# CristmasVillage_Driver_1-0.net
KiCad netlist of a schematic drawn in EAGLE
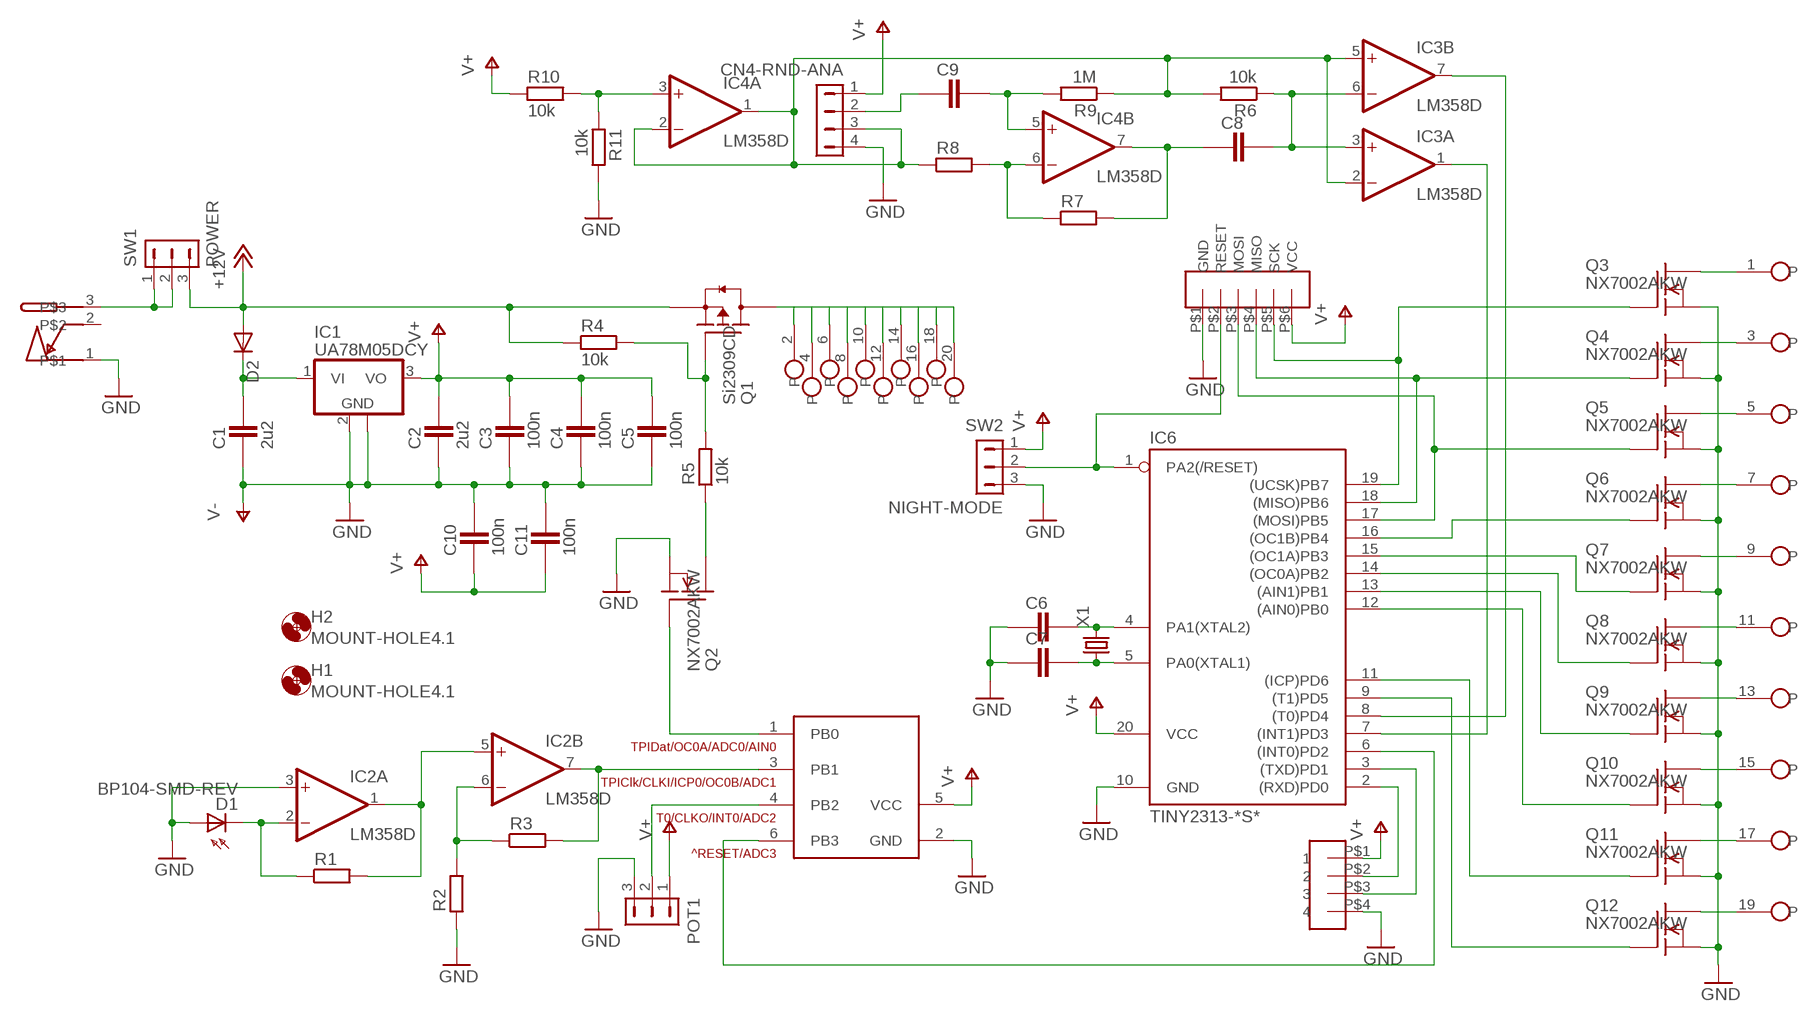
[diagram p0: schematic, sheet 1]

(export (version "E")
  (design (tool "Eeschema 10.0.6"))
  (components
    (comp (ref "C1")
      (value "2u2")
      (footprint "eagle-import:CAPC3215X168N")
      (libsource (lib "eagle-import") (part "CAPACITOR_1206"))
    )
    (comp (ref "C2")
      (value "2u2")
      (footprint "eagle-import:CAPC3215X168N")
      (libsource (lib "eagle-import") (part "CAPACITOR_1206"))
    )
    (comp (ref "C3")
      (value "100n")
      (footprint "eagle-import:CAPC1608X92N")
      (libsource (lib "eagle-import") (part "CAPACITOR_0603"))
    )
    (comp (ref "C4")
      (value "100n")
      (footprint "eagle-import:CAPC1608X92N")
      (libsource (lib "eagle-import") (part "CAPACITOR_0603"))
    )
    (comp (ref "C5")
      (value "100n")
      (footprint "eagle-import:CAPC1608X92N")
      (libsource (lib "eagle-import") (part "CAPACITOR_0603"))
    )
    (comp (ref "C6")
      (value "CAPACITOR_0603")
      (footprint "eagle-import:CAPC1608X92N")
      (libsource (lib "eagle-import") (part "CAPACITOR_0603"))
    )
    (comp (ref "C7")
      (value "CAPACITOR_0603")
      (footprint "eagle-import:CAPC1608X92N")
      (libsource (lib "eagle-import") (part "CAPACITOR_0603"))
    )
    (comp (ref "C8")
      (value "CAPACITOR_1206")
      (footprint "eagle-import:CAPC3215X168N")
      (libsource (lib "eagle-import") (part "CAPACITOR_1206"))
    )
    (comp (ref "C9")
      (value "CAPACITOR_1206")
      (footprint "eagle-import:CAPC3215X168N")
      (libsource (lib "eagle-import") (part "CAPACITOR_1206"))
    )
    (comp (ref "C10")
      (value "100n")
      (footprint "eagle-import:CAPC1608X92N")
      (libsource (lib "eagle-import") (part "CAPACITOR_0603"))
    )
    (comp (ref "C11")
      (value "100n")
      (footprint "eagle-import:CAPC1608X92N")
      (libsource (lib "eagle-import") (part "CAPACITOR_0603"))
    )
    (comp (ref "CN1")
      (value "MJ-180SMT")
      (footprint "eagle-import:MJ-180SMT")
      (libsource (lib "eagle-import") (part "MJ-180SMT"))
    )
    (comp (ref "CN2-PROG")
      (value "JST-6PSPI-SIDE-S6B")
      (footprint "eagle-import:6P-H")
      (libsource (lib "eagle-import") (part "JST-6PSPI-SIDE-S6B"))
    )
    (comp (ref "CN3-SERIAL")
      (value "JST-4PSIDE-S4B")
      (footprint "eagle-import:4P-H")
      (libsource (lib "eagle-import") (part "JST-4PSIDE-S4B"))
    )
    (comp (ref "CN4-RND-ANA")
      (value "HDR-1X4-SIP-100")
      (footprint "eagle-import:SIP-100-4V")
      (libsource (lib "eagle-import") (part "HDR-1X4-SIP-100"))
    )
    (comp (ref "CN5-LEDSTRIPS")
      (value "HDR_2X10_SIDE-MOUNT")
      (footprint "eagle-import:20PIN-10TOP-10BOT")
      (libsource (lib "eagle-import") (part "HDR_2X10_SIDE-MOUNT"))
    )
    (comp (ref "D1")
      (value "BP104-SMD-REV")
      (footprint "eagle-import:BR104SMDREV")
      (libsource (lib "eagle-import") (part "BP104-SMD-REV"))
    )
    (comp (ref "D2")
      (value "DIODE-MINIMELF")
      (footprint "eagle-import:MINIMELF")
      (libsource (lib "eagle-import") (part "DIODE-MINIMELF"))
    )
    (comp (ref "H1")
      (value "MOUNT-HOLE4.1")
      (footprint "eagle-import:4,1")
      (libsource (lib "eagle-import") (part "MOUNT-HOLE4.1"))
    )
    (comp (ref "H2")
      (value "MOUNT-HOLE4.1")
      (footprint "eagle-import:4,1")
      (libsource (lib "eagle-import") (part "MOUNT-HOLE4.1"))
    )
    (comp (ref "IC1")
      (value "UA78M05DCY")
      (footprint "eagle-import:SOT223")
      (libsource (lib "eagle-import") (part "UA78MDCY05"))
    )
    (comp (ref "IC2")
      (value "LM358D")
      (footprint "eagle-import:SO08")
      (libsource (lib "eagle-import") (part "LM358D"))
    )
    (comp (ref "IC3")
      (value "LM358D")
      (footprint "eagle-import:SO08")
      (libsource (lib "eagle-import") (part "LM358D"))
    )
    (comp (ref "IC4")
      (value "LM358D")
      (footprint "eagle-import:SO08")
      (libsource (lib "eagle-import") (part "LM358D"))
    )
    (comp (ref "IC5")
      (value "ATTINY-4/5/9/10")
      (footprint "eagle-import:SOT23-6")
      (libsource (lib "eagle-import") (part "ATTINY-4/5/9/10"))
    )
    (comp (ref "IC6")
      (value "TINY2313-*S*")
      (footprint "eagle-import:SO20L$")
      (libsource (lib "eagle-import") (part "TINY2313-S"))
    )
    (comp (ref "POT1")
      (value "HDR-1X3-MTE-100")
      (footprint "eagle-import:MTE-100-3V")
      (libsource (lib "eagle-import") (part "HDR-1X3-MTE-100"))
    )
    (comp (ref "Q1")
      (value "Si2309CD")
      (footprint "eagle-import:SOT95P280X135-3N")
      (libsource (lib "eagle-import") (part "MOSFET-PCH_SOT-23"))
    )
    (comp (ref "Q2")
      (value "NX7002AKW")
      (footprint "eagle-import:SOT323R")
      (libsource (lib "eagle-import") (part "NX7002AKW"))
    )
    (comp (ref "Q3")
      (value "NX7002AKW")
      (footprint "eagle-import:SOT323R")
      (libsource (lib "eagle-import") (part "NX7002AKW"))
    )
    (comp (ref "Q4")
      (value "NX7002AKW")
      (footprint "eagle-import:SOT323R")
      (libsource (lib "eagle-import") (part "NX7002AKW"))
    )
    (comp (ref "Q5")
      (value "NX7002AKW")
      (footprint "eagle-import:SOT323R")
      (libsource (lib "eagle-import") (part "NX7002AKW"))
    )
    (comp (ref "Q6")
      (value "NX7002AKW")
      (footprint "eagle-import:SOT323R")
      (libsource (lib "eagle-import") (part "NX7002AKW"))
    )
    (comp (ref "Q7")
      (value "NX7002AKW")
      (footprint "eagle-import:SOT323R")
      (libsource (lib "eagle-import") (part "NX7002AKW"))
    )
    (comp (ref "Q8")
      (value "NX7002AKW")
      (footprint "eagle-import:SOT323R")
      (libsource (lib "eagle-import") (part "NX7002AKW"))
    )
    (comp (ref "Q9")
      (value "NX7002AKW")
      (footprint "eagle-import:SOT323R")
      (libsource (lib "eagle-import") (part "NX7002AKW"))
    )
    (comp (ref "Q10")
      (value "NX7002AKW")
      (footprint "eagle-import:SOT323R")
      (libsource (lib "eagle-import") (part "NX7002AKW"))
    )
    (comp (ref "Q11")
      (value "NX7002AKW")
      (footprint "eagle-import:SOT323R")
      (libsource (lib "eagle-import") (part "NX7002AKW"))
    )
    (comp (ref "Q12")
      (value "NX7002AKW")
      (footprint "eagle-import:SOT323R")
      (libsource (lib "eagle-import") (part "NX7002AKW"))
    )
    (comp (ref "R1")
      (value "RESISTOR_0603")
      (footprint "eagle-import:RESC1608X55N")
      (libsource (lib "eagle-import") (part "RESISTOR_0603"))
    )
    (comp (ref "R2")
      (value "RESISTOR_0603")
      (footprint "eagle-import:RESC1608X55N")
      (libsource (lib "eagle-import") (part "RESISTOR_0603"))
    )
    (comp (ref "R3")
      (value "RESISTOR_0603")
      (footprint "eagle-import:RESC1608X55N")
      (libsource (lib "eagle-import") (part "RESISTOR_0603"))
    )
    (comp (ref "R4")
      (value "10k")
      (footprint "eagle-import:RESC1608X55N")
      (libsource (lib "eagle-import") (part "RESISTOR_0603"))
    )
    (comp (ref "R5")
      (value "10k")
      (footprint "eagle-import:RESC1608X55N")
      (libsource (lib "eagle-import") (part "RESISTOR_0603"))
    )
    (comp (ref "R6")
      (value "10k")
      (footprint "eagle-import:RESC1608X55N")
      (libsource (lib "eagle-import") (part "RESISTOR_0603"))
    )
    (comp (ref "R7")
      (value "RESISTOR_0603")
      (footprint "eagle-import:RESC1608X55N")
      (libsource (lib "eagle-import") (part "RESISTOR_0603"))
    )
    (comp (ref "R8")
      (value "RESISTOR_0603")
      (footprint "eagle-import:RESC1608X55N")
      (libsource (lib "eagle-import") (part "RESISTOR_0603"))
    )
    (comp (ref "R9")
      (value "1M")
      (footprint "eagle-import:RESC1608X55N")
      (libsource (lib "eagle-import") (part "RESISTOR_0603"))
    )
    (comp (ref "R10")
      (value "10k")
      (footprint "eagle-import:RESC1608X55N")
      (libsource (lib "eagle-import") (part "RESISTOR_0603"))
    )
    (comp (ref "R11")
      (value "10k")
      (footprint "eagle-import:RESC1608X55N")
      (libsource (lib "eagle-import") (part "RESISTOR_0603"))
    )
    (comp (ref "SW1")
      (value "POWER")
      (footprint "eagle-import:MTE-100-3V")
      (libsource (lib "eagle-import") (part "HDR-1X3-MTE-100"))
    )
    (comp (ref "SW2")
      (value "NIGHT-MODE")
      (footprint "eagle-import:MTE-100-3V")
      (libsource (lib "eagle-import") (part "HDR-1X3-MTE-100"))
    )
    (comp (ref "X1")
      (value "CRYSTALSM49")
      (footprint "eagle-import:SM49")
      (libsource (lib "eagle-import") (part "CRYSTALSM49"))
    )
  )
  (nets
    (net (code "1") (name "+12V") (class "Default")
      (node (ref "D2") (pin "A") (pinfunction "A_A") (pintype "passive"))
      (node (ref "Q1") (pin "2") (pinfunction "S_2") (pintype "passive"))
      (node (ref "R4") (pin "1") (pinfunction "1_1") (pintype "passive"))
      (node (ref "SW1") (pin "3") (pinfunction "3_3") (pintype "passive"))
    )
    (net (code "2") (name "GND") (class "Default")
      (node (ref "C1") (pin "1") (pinfunction "1_1") (pintype "passive"))
      (node (ref "C10") (pin "2") (pinfunction "2_2") (pintype "passive"))
      (node (ref "C11") (pin "2") (pinfunction "2_2") (pintype "passive"))
      (node (ref "C2") (pin "1") (pinfunction "1_1") (pintype "passive"))
      (node (ref "C3") (pin "1") (pinfunction "1_1") (pintype "passive"))
      (node (ref "C4") (pin "1") (pinfunction "1_1") (pintype "passive"))
      (node (ref "C5") (pin "1") (pinfunction "1_1") (pintype "passive"))
      (node (ref "C6") (pin "1") (pinfunction "1_1") (pintype "passive"))
      (node (ref "C7") (pin "1") (pinfunction "1_1") (pintype "passive"))
      (node (ref "CN1") (pin "1") (pinfunction "P$1_1") (pintype "bidirectional"))
      (node (ref "CN2-PROG") (pin "P$1") (pinfunction "GND_P$1") (pintype "bidirectional"))
      (node (ref "CN3-SERIAL") (pin "P$4") (pinfunction "4_P$4") (pintype "bidirectional"))
      (node (ref "CN4-RND-ANA") (pin "4") (pinfunction "4_4") (pintype "passive"))
      (node (ref "D1") (pin "1") (pinfunction "A_1") (pintype "passive"))
      (node (ref "IC1") (pin "2") (pinfunction "GND_2") (pintype "passive"))
      (node (ref "IC1") (pin "4") (pinfunction "GND_4") (pintype "passive"))
      (node (ref "IC2") (pin "3") (pinfunction "+IN_3") (pintype "input"))
      (node (ref "IC5") (pin "2") (pinfunction "GND_2") (pintype "bidirectional"))
      (node (ref "IC6") (pin "10") (pinfunction "GND_10") (pintype "power_in"))
      (node (ref "POT1") (pin "3") (pinfunction "3_3") (pintype "passive"))
      (node (ref "Q10") (pin "2") (pinfunction "S_2") (pintype "passive"))
      (node (ref "Q11") (pin "2") (pinfunction "S_2") (pintype "passive"))
      (node (ref "Q12") (pin "2") (pinfunction "S_2") (pintype "passive"))
      (node (ref "Q2") (pin "2") (pinfunction "S_2") (pintype "passive"))
      (node (ref "Q3") (pin "2") (pinfunction "S_2") (pintype "passive"))
      (node (ref "Q4") (pin "2") (pinfunction "S_2") (pintype "passive"))
      (node (ref "Q5") (pin "2") (pinfunction "S_2") (pintype "passive"))
      (node (ref "Q6") (pin "2") (pinfunction "S_2") (pintype "passive"))
      (node (ref "Q7") (pin "2") (pinfunction "S_2") (pintype "passive"))
      (node (ref "Q8") (pin "2") (pinfunction "S_2") (pintype "passive"))
      (node (ref "Q9") (pin "2") (pinfunction "S_2") (pintype "passive"))
      (node (ref "R11") (pin "2") (pinfunction "2_2") (pintype "passive"))
      (node (ref "R2") (pin "1") (pinfunction "1_1") (pintype "passive"))
      (node (ref "SW2") (pin "3") (pinfunction "3_3") (pintype "passive"))
    )
    (net (code "3") (name "Net-(C9-Pad1)") (class "Default")
      (node (ref "C9") (pin "1") (pinfunction "1_1") (pintype "passive"))
      (node (ref "CN4-RND-ANA") (pin "2") (pinfunction "2_2") (pintype "passive"))
    )
    (net (code "4") (name "Net-(CN1-P$3)") (class "Default")
      (node (ref "CN1") (pin "3") (pinfunction "P$3_3") (pintype "bidirectional"))
      (node (ref "SW1") (pin "1") (pinfunction "1_1") (pintype "passive"))
      (node (ref "SW1") (pin "2") (pinfunction "2_2") (pintype "passive"))
    )
    (net (code "5") (name "Net-(CN2-PROG-MISO)") (class "Default")
      (node (ref "CN2-PROG") (pin "P$4") (pinfunction "MISO_P$4") (pintype "bidirectional"))
      (node (ref "IC6") (pin "18") (pinfunction "(MISO)PB6_18") (pintype "bidirectional"))
      (node (ref "Q4") (pin "1") (pinfunction "G_1") (pintype "passive"))
    )
    (net (code "6") (name "Net-(CN2-PROG-MOSI)") (class "Default")
      (node (ref "CN2-PROG") (pin "P$3") (pinfunction "MOSI_P$3") (pintype "bidirectional"))
      (node (ref "IC6") (pin "17") (pinfunction "(MOSI)PB5_17") (pintype "bidirectional"))
      (node (ref "Q5") (pin "1") (pinfunction "G_1") (pintype "passive"))
    )
    (net (code "7") (name "Net-(CN2-PROG-RESET)") (class "Default")
      (node (ref "CN2-PROG") (pin "P$2") (pinfunction "RESET_P$2") (pintype "bidirectional"))
      (node (ref "IC6") (pin "1") (pinfunction "PA2(/RESET)_1") (pintype "input"))
      (node (ref "SW2") (pin "2") (pinfunction "2_2") (pintype "passive"))
    )
    (net (code "8") (name "Net-(CN2-PROG-SCK)") (class "Default")
      (node (ref "CN2-PROG") (pin "P$5") (pinfunction "SCK_P$5") (pintype "bidirectional"))
      (node (ref "IC6") (pin "19") (pinfunction "(UCSK)PB7_19") (pintype "bidirectional"))
      (node (ref "Q3") (pin "1") (pinfunction "G_1") (pintype "passive"))
    )
    (net (code "9") (name "Net-(CN3-SERIAL-2)") (class "Default")
      (node (ref "CN3-SERIAL") (pin "P$2") (pinfunction "2_P$2") (pintype "bidirectional"))
      (node (ref "IC6") (pin "2") (pinfunction "(RXD)PD0_2") (pintype "bidirectional"))
    )
    (net (code "10") (name "Net-(CN3-SERIAL-3)") (class "Default")
      (node (ref "CN3-SERIAL") (pin "P$3") (pinfunction "3_P$3") (pintype "bidirectional"))
      (node (ref "IC6") (pin "3") (pinfunction "(TXD)PD1_3") (pintype "bidirectional"))
    )
    (net (code "11") (name "Net-(CN5-LEDSTRIPSA-P)") (class "Default")
      (node (ref "CN5-LEDSTRIPS") (pin "1") (pinfunction "P_1") (pintype "bidirectional"))
      (node (ref "Q3") (pin "3") (pinfunction "D_3") (pintype "passive"))
    )
    (net (code "12") (name "Net-(CN5-LEDSTRIPSB-P)") (class "Default")
      (node (ref "CN5-LEDSTRIPS") (pin "10") (pinfunction "P_10") (pintype "bidirectional"))
      (node (ref "CN5-LEDSTRIPS") (pin "12") (pinfunction "P_12") (pintype "bidirectional"))
      (node (ref "CN5-LEDSTRIPS") (pin "14") (pinfunction "P_14") (pintype "bidirectional"))
      (node (ref "CN5-LEDSTRIPS") (pin "16") (pinfunction "P_16") (pintype "bidirectional"))
      (node (ref "CN5-LEDSTRIPS") (pin "18") (pinfunction "P_18") (pintype "bidirectional"))
      (node (ref "CN5-LEDSTRIPS") (pin "2") (pinfunction "P_2") (pintype "bidirectional"))
      (node (ref "CN5-LEDSTRIPS") (pin "20") (pinfunction "P_20") (pintype "bidirectional"))
      (node (ref "CN5-LEDSTRIPS") (pin "4") (pinfunction "P_4") (pintype "bidirectional"))
      (node (ref "CN5-LEDSTRIPS") (pin "6") (pinfunction "P_6") (pintype "bidirectional"))
      (node (ref "CN5-LEDSTRIPS") (pin "8") (pinfunction "P_8") (pintype "bidirectional"))
      (node (ref "Q1") (pin "3") (pinfunction "D_3") (pintype "passive"))
    )
    (net (code "13") (name "Net-(CN5-LEDSTRIPSC-P)") (class "Default")
      (node (ref "CN5-LEDSTRIPS") (pin "11") (pinfunction "P_11") (pintype "bidirectional"))
      (node (ref "Q8") (pin "3") (pinfunction "D_3") (pintype "passive"))
    )
    (net (code "14") (name "Net-(CN5-LEDSTRIPSE-P)") (class "Default")
      (node (ref "CN5-LEDSTRIPS") (pin "13") (pinfunction "P_13") (pintype "bidirectional"))
      (node (ref "Q9") (pin "3") (pinfunction "D_3") (pintype "passive"))
    )
    (net (code "15") (name "Net-(CN5-LEDSTRIPSG-P)") (class "Default")
      (node (ref "CN5-LEDSTRIPS") (pin "15") (pinfunction "P_15") (pintype "bidirectional"))
      (node (ref "Q10") (pin "3") (pinfunction "D_3") (pintype "passive"))
    )
    (net (code "16") (name "Net-(CN5-LEDSTRIPSI-P)") (class "Default")
      (node (ref "CN5-LEDSTRIPS") (pin "17") (pinfunction "P_17") (pintype "bidirectional"))
      (node (ref "Q11") (pin "3") (pinfunction "D_3") (pintype "passive"))
    )
    (net (code "17") (name "Net-(CN5-LEDSTRIPSK-P)") (class "Default")
      (node (ref "CN5-LEDSTRIPS") (pin "19") (pinfunction "P_19") (pintype "bidirectional"))
      (node (ref "Q12") (pin "3") (pinfunction "D_3") (pintype "passive"))
    )
    (net (code "18") (name "Net-(CN5-LEDSTRIPSN-P)") (class "Default")
      (node (ref "CN5-LEDSTRIPS") (pin "3") (pinfunction "P_3") (pintype "bidirectional"))
      (node (ref "Q4") (pin "3") (pinfunction "D_3") (pintype "passive"))
    )
    (net (code "19") (name "Net-(CN5-LEDSTRIPSP-P)") (class "Default")
      (node (ref "CN5-LEDSTRIPS") (pin "5") (pinfunction "P_5") (pintype "bidirectional"))
      (node (ref "Q5") (pin "3") (pinfunction "D_3") (pintype "passive"))
    )
    (net (code "20") (name "Net-(CN5-LEDSTRIPSR-P)") (class "Default")
      (node (ref "CN5-LEDSTRIPS") (pin "7") (pinfunction "P_7") (pintype "bidirectional"))
      (node (ref "Q6") (pin "3") (pinfunction "D_3") (pintype "passive"))
    )
    (net (code "21") (name "Net-(CN5-LEDSTRIPST-P)") (class "Default")
      (node (ref "CN5-LEDSTRIPS") (pin "9") (pinfunction "P_9") (pintype "bidirectional"))
      (node (ref "Q7") (pin "3") (pinfunction "D_3") (pintype "passive"))
    )
    (net (code "22") (name "Net-(D1-C)") (class "Default")
      (node (ref "D1") (pin "2") (pinfunction "C_2") (pintype "passive"))
      (node (ref "IC2") (pin "2") (pinfunction "-IN_2") (pintype "input"))
      (node (ref "R1") (pin "1") (pinfunction "1_1") (pintype "passive"))
    )
    (net (code "23") (name "Net-(IC1-VI)") (class "Default")
      (node (ref "C1") (pin "2") (pinfunction "2_2") (pintype "passive"))
      (node (ref "D2") (pin "C") (pinfunction "C_C") (pintype "passive"))
      (node (ref "IC1") (pin "1") (pinfunction "VI_1") (pintype "input"))
    )
    (net (code "24") (name "Net-(IC2A-OUT)") (class "Default")
      (node (ref "IC2") (pin "1") (pinfunction "OUT_1") (pintype "output"))
      (node (ref "IC2") (pin "5") (pinfunction "+IN_5") (pintype "input"))
      (node (ref "R1") (pin "2") (pinfunction "2_2") (pintype "passive"))
    )
    (net (code "25") (name "Net-(IC2B--IN)") (class "Default")
      (node (ref "IC2") (pin "6") (pinfunction "-IN_6") (pintype "input"))
      (node (ref "R2") (pin "2") (pinfunction "2_2") (pintype "passive"))
      (node (ref "R3") (pin "1") (pinfunction "1_1") (pintype "passive"))
    )
    (net (code "26") (name "Net-(IC2B-OUT)") (class "Default")
      (node (ref "IC2") (pin "7") (pinfunction "OUT_7") (pintype "output"))
      (node (ref "IC5") (pin "3") (pinfunction "PB1_3") (pintype "bidirectional"))
      (node (ref "R3") (pin "2") (pinfunction "2_2") (pintype "passive"))
    )
    (net (code "27") (name "Net-(IC3A-+IN)") (class "Default")
      (node (ref "C8") (pin "2") (pinfunction "2_2") (pintype "passive"))
      (node (ref "IC3") (pin "3") (pinfunction "+IN_3") (pintype "input"))
      (node (ref "IC3") (pin "6") (pinfunction "-IN_6") (pintype "input"))
      (node (ref "R6") (pin "1") (pinfunction "1_1") (pintype "passive"))
    )
    (net (code "28") (name "Net-(IC3A--IN)") (class "Default")
      (node (ref "CN4-RND-ANA") (pin "3") (pinfunction "3_3") (pintype "passive"))
      (node (ref "IC3") (pin "2") (pinfunction "-IN_2") (pintype "input"))
      (node (ref "IC3") (pin "5") (pinfunction "+IN_5") (pintype "input"))
      (node (ref "IC4") (pin "1") (pinfunction "OUT_1") (pintype "output"))
      (node (ref "IC4") (pin "2") (pinfunction "-IN_2") (pintype "input"))
      (node (ref "R6") (pin "2") (pinfunction "2_2") (pintype "passive"))
      (node (ref "R8") (pin "1") (pinfunction "1_1") (pintype "passive"))
      (node (ref "R9") (pin "1") (pinfunction "1_1") (pintype "passive"))
    )
    (net (code "29") (name "Net-(IC3A-OUT)") (class "Default")
      (node (ref "IC3") (pin "1") (pinfunction "OUT_1") (pintype "output"))
      (node (ref "IC6") (pin "7") (pinfunction "(INT1)PD3_7") (pintype "bidirectional"))
    )
    (net (code "30") (name "Net-(IC3B-OUT)") (class "Default")
      (node (ref "IC3") (pin "7") (pinfunction "OUT_7") (pintype "output"))
      (node (ref "IC6") (pin "8") (pinfunction "(T0)PD4_8") (pintype "bidirectional"))
    )
    (net (code "31") (name "Net-(IC4A-+IN)") (class "Default")
      (node (ref "IC4") (pin "3") (pinfunction "+IN_3") (pintype "input"))
      (node (ref "R10") (pin "2") (pinfunction "2_2") (pintype "passive"))
      (node (ref "R11") (pin "1") (pinfunction "1_1") (pintype "passive"))
    )
    (net (code "32") (name "Net-(IC4B-+IN)") (class "Default")
      (node (ref "C9") (pin "2") (pinfunction "2_2") (pintype "passive"))
      (node (ref "IC4") (pin "5") (pinfunction "+IN_5") (pintype "input"))
      (node (ref "R9") (pin "2") (pinfunction "2_2") (pintype "passive"))
    )
    (net (code "33") (name "Net-(IC4B--IN)") (class "Default")
      (node (ref "IC4") (pin "6") (pinfunction "-IN_6") (pintype "input"))
      (node (ref "R7") (pin "1") (pinfunction "1_1") (pintype "passive"))
      (node (ref "R8") (pin "2") (pinfunction "2_2") (pintype "passive"))
    )
    (net (code "34") (name "Net-(IC4B-OUT)") (class "Default")
      (node (ref "C8") (pin "1") (pinfunction "1_1") (pintype "passive"))
      (node (ref "IC4") (pin "7") (pinfunction "OUT_7") (pintype "output"))
      (node (ref "R7") (pin "2") (pinfunction "2_2") (pintype "passive"))
    )
    (net (code "35") (name "Net-(IC5-PB0)") (class "Default")
      (node (ref "IC5") (pin "1") (pinfunction "PB0_1") (pintype "bidirectional"))
      (node (ref "Q2") (pin "1") (pinfunction "G_1") (pintype "passive"))
    )
    (net (code "36") (name "Net-(IC5-PB2)") (class "Default")
      (node (ref "IC5") (pin "4") (pinfunction "PB2_4") (pintype "bidirectional"))
      (node (ref "POT1") (pin "2") (pinfunction "2_2") (pintype "passive"))
    )
    (net (code "37") (name "Net-(IC5-PB3)") (class "Default")
      (node (ref "IC5") (pin "6") (pinfunction "PB3_6") (pintype "bidirectional"))
      (node (ref "IC6") (pin "6") (pinfunction "(INT0)PD2_6") (pintype "bidirectional"))
    )
    (net (code "38") (name "Net-(IC6-(AIN0)PB0)") (class "Default")
      (node (ref "IC6") (pin "12") (pinfunction "(AIN0)PB0_12") (pintype "bidirectional"))
      (node (ref "Q10") (pin "1") (pinfunction "G_1") (pintype "passive"))
    )
    (net (code "39") (name "Net-(IC6-(AIN1)PB1)") (class "Default")
      (node (ref "IC6") (pin "13") (pinfunction "(AIN1)PB1_13") (pintype "bidirectional"))
      (node (ref "Q9") (pin "1") (pinfunction "G_1") (pintype "passive"))
    )
    (net (code "40") (name "Net-(IC6-(ICP)PD6)") (class "Default")
      (node (ref "IC6") (pin "11") (pinfunction "(ICP)PD6_11") (pintype "bidirectional"))
      (node (ref "Q11") (pin "1") (pinfunction "G_1") (pintype "passive"))
    )
    (net (code "41") (name "Net-(IC6-(OC0A)PB2)") (class "Default")
      (node (ref "IC6") (pin "14") (pinfunction "(OC0A)PB2_14") (pintype "bidirectional"))
      (node (ref "Q8") (pin "1") (pinfunction "G_1") (pintype "passive"))
    )
    (net (code "42") (name "Net-(IC6-(OC1A)PB3)") (class "Default")
      (node (ref "IC6") (pin "15") (pinfunction "(OC1A)PB3_15") (pintype "bidirectional"))
      (node (ref "Q7") (pin "1") (pinfunction "G_1") (pintype "passive"))
    )
    (net (code "43") (name "Net-(IC6-(OC1B)PB4)") (class "Default")
      (node (ref "IC6") (pin "16") (pinfunction "(OC1B)PB4_16") (pintype "bidirectional"))
      (node (ref "Q6") (pin "1") (pinfunction "G_1") (pintype "passive"))
    )
    (net (code "44") (name "Net-(IC6-(T1)PD5)") (class "Default")
      (node (ref "IC6") (pin "9") (pinfunction "(T1)PD5_9") (pintype "bidirectional"))
      (node (ref "Q12") (pin "1") (pinfunction "G_1") (pintype "passive"))
    )
    (net (code "45") (name "Net-(IC6-PA0(XTAL1))") (class "Default")
      (node (ref "C7") (pin "2") (pinfunction "2_2") (pintype "passive"))
      (node (ref "IC6") (pin "5") (pinfunction "PA0(XTAL1)_5") (pintype "bidirectional"))
      (node (ref "X1") (pin "1") (pinfunction "1_1") (pintype "passive"))
    )
    (net (code "46") (name "Net-(IC6-PA1(XTAL2))") (class "Default")
      (node (ref "C6") (pin "2") (pinfunction "2_2") (pintype "passive"))
      (node (ref "IC6") (pin "4") (pinfunction "PA1(XTAL2)_4") (pintype "bidirectional"))
      (node (ref "X1") (pin "2") (pinfunction "2_2") (pintype "passive"))
    )
    (net (code "47") (name "Net-(Q1-G)") (class "Default")
      (node (ref "Q1") (pin "1") (pinfunction "G_1") (pintype "passive"))
      (node (ref "R4") (pin "2") (pinfunction "2_2") (pintype "passive"))
      (node (ref "R5") (pin "2") (pinfunction "2_2") (pintype "passive"))
    )
    (net (code "48") (name "Net-(Q2-D)") (class "Default")
      (node (ref "Q2") (pin "3") (pinfunction "D_3") (pintype "passive"))
      (node (ref "R5") (pin "1") (pinfunction "1_1") (pintype "passive"))
    )
    (net (code "49") (name "V+") (class "Default")
      (node (ref "C10") (pin "1") (pinfunction "1_1") (pintype "passive"))
      (node (ref "C11") (pin "1") (pinfunction "1_1") (pintype "passive"))
      (node (ref "C2") (pin "2") (pinfunction "2_2") (pintype "passive"))
      (node (ref "C3") (pin "2") (pinfunction "2_2") (pintype "passive"))
      (node (ref "C4") (pin "2") (pinfunction "2_2") (pintype "passive"))
      (node (ref "C5") (pin "2") (pinfunction "2_2") (pintype "passive"))
      (node (ref "CN2-PROG") (pin "P$6") (pinfunction "VCC_P$6") (pintype "bidirectional"))
      (node (ref "CN3-SERIAL") (pin "P$1") (pinfunction "1_P$1") (pintype "bidirectional"))
      (node (ref "CN4-RND-ANA") (pin "1") (pinfunction "1_1") (pintype "passive"))
      (node (ref "IC1") (pin "3") (pinfunction "VO_3") (pintype "passive"))
      (node (ref "IC5") (pin "5") (pinfunction "VCC_5") (pintype "bidirectional"))
      (node (ref "IC6") (pin "20") (pinfunction "VCC_20") (pintype "power_in"))
      (node (ref "POT1") (pin "1") (pinfunction "1_1") (pintype "passive"))
      (node (ref "R10") (pin "1") (pinfunction "1_1") (pintype "passive"))
      (node (ref "SW2") (pin "1") (pinfunction "1_1") (pintype "passive"))
    )
    (net (code "50") (name "unconnected-(CN1-P$2-Pad2)") (class "Default")
      (node (ref "CN1") (pin "2") (pinfunction "P$2_2") (pintype "bidirectional"))
    )
  )
)
